# esp32_phiccamdien.net
KiCad netlist of a schematic drawn in EasyEDA Pro
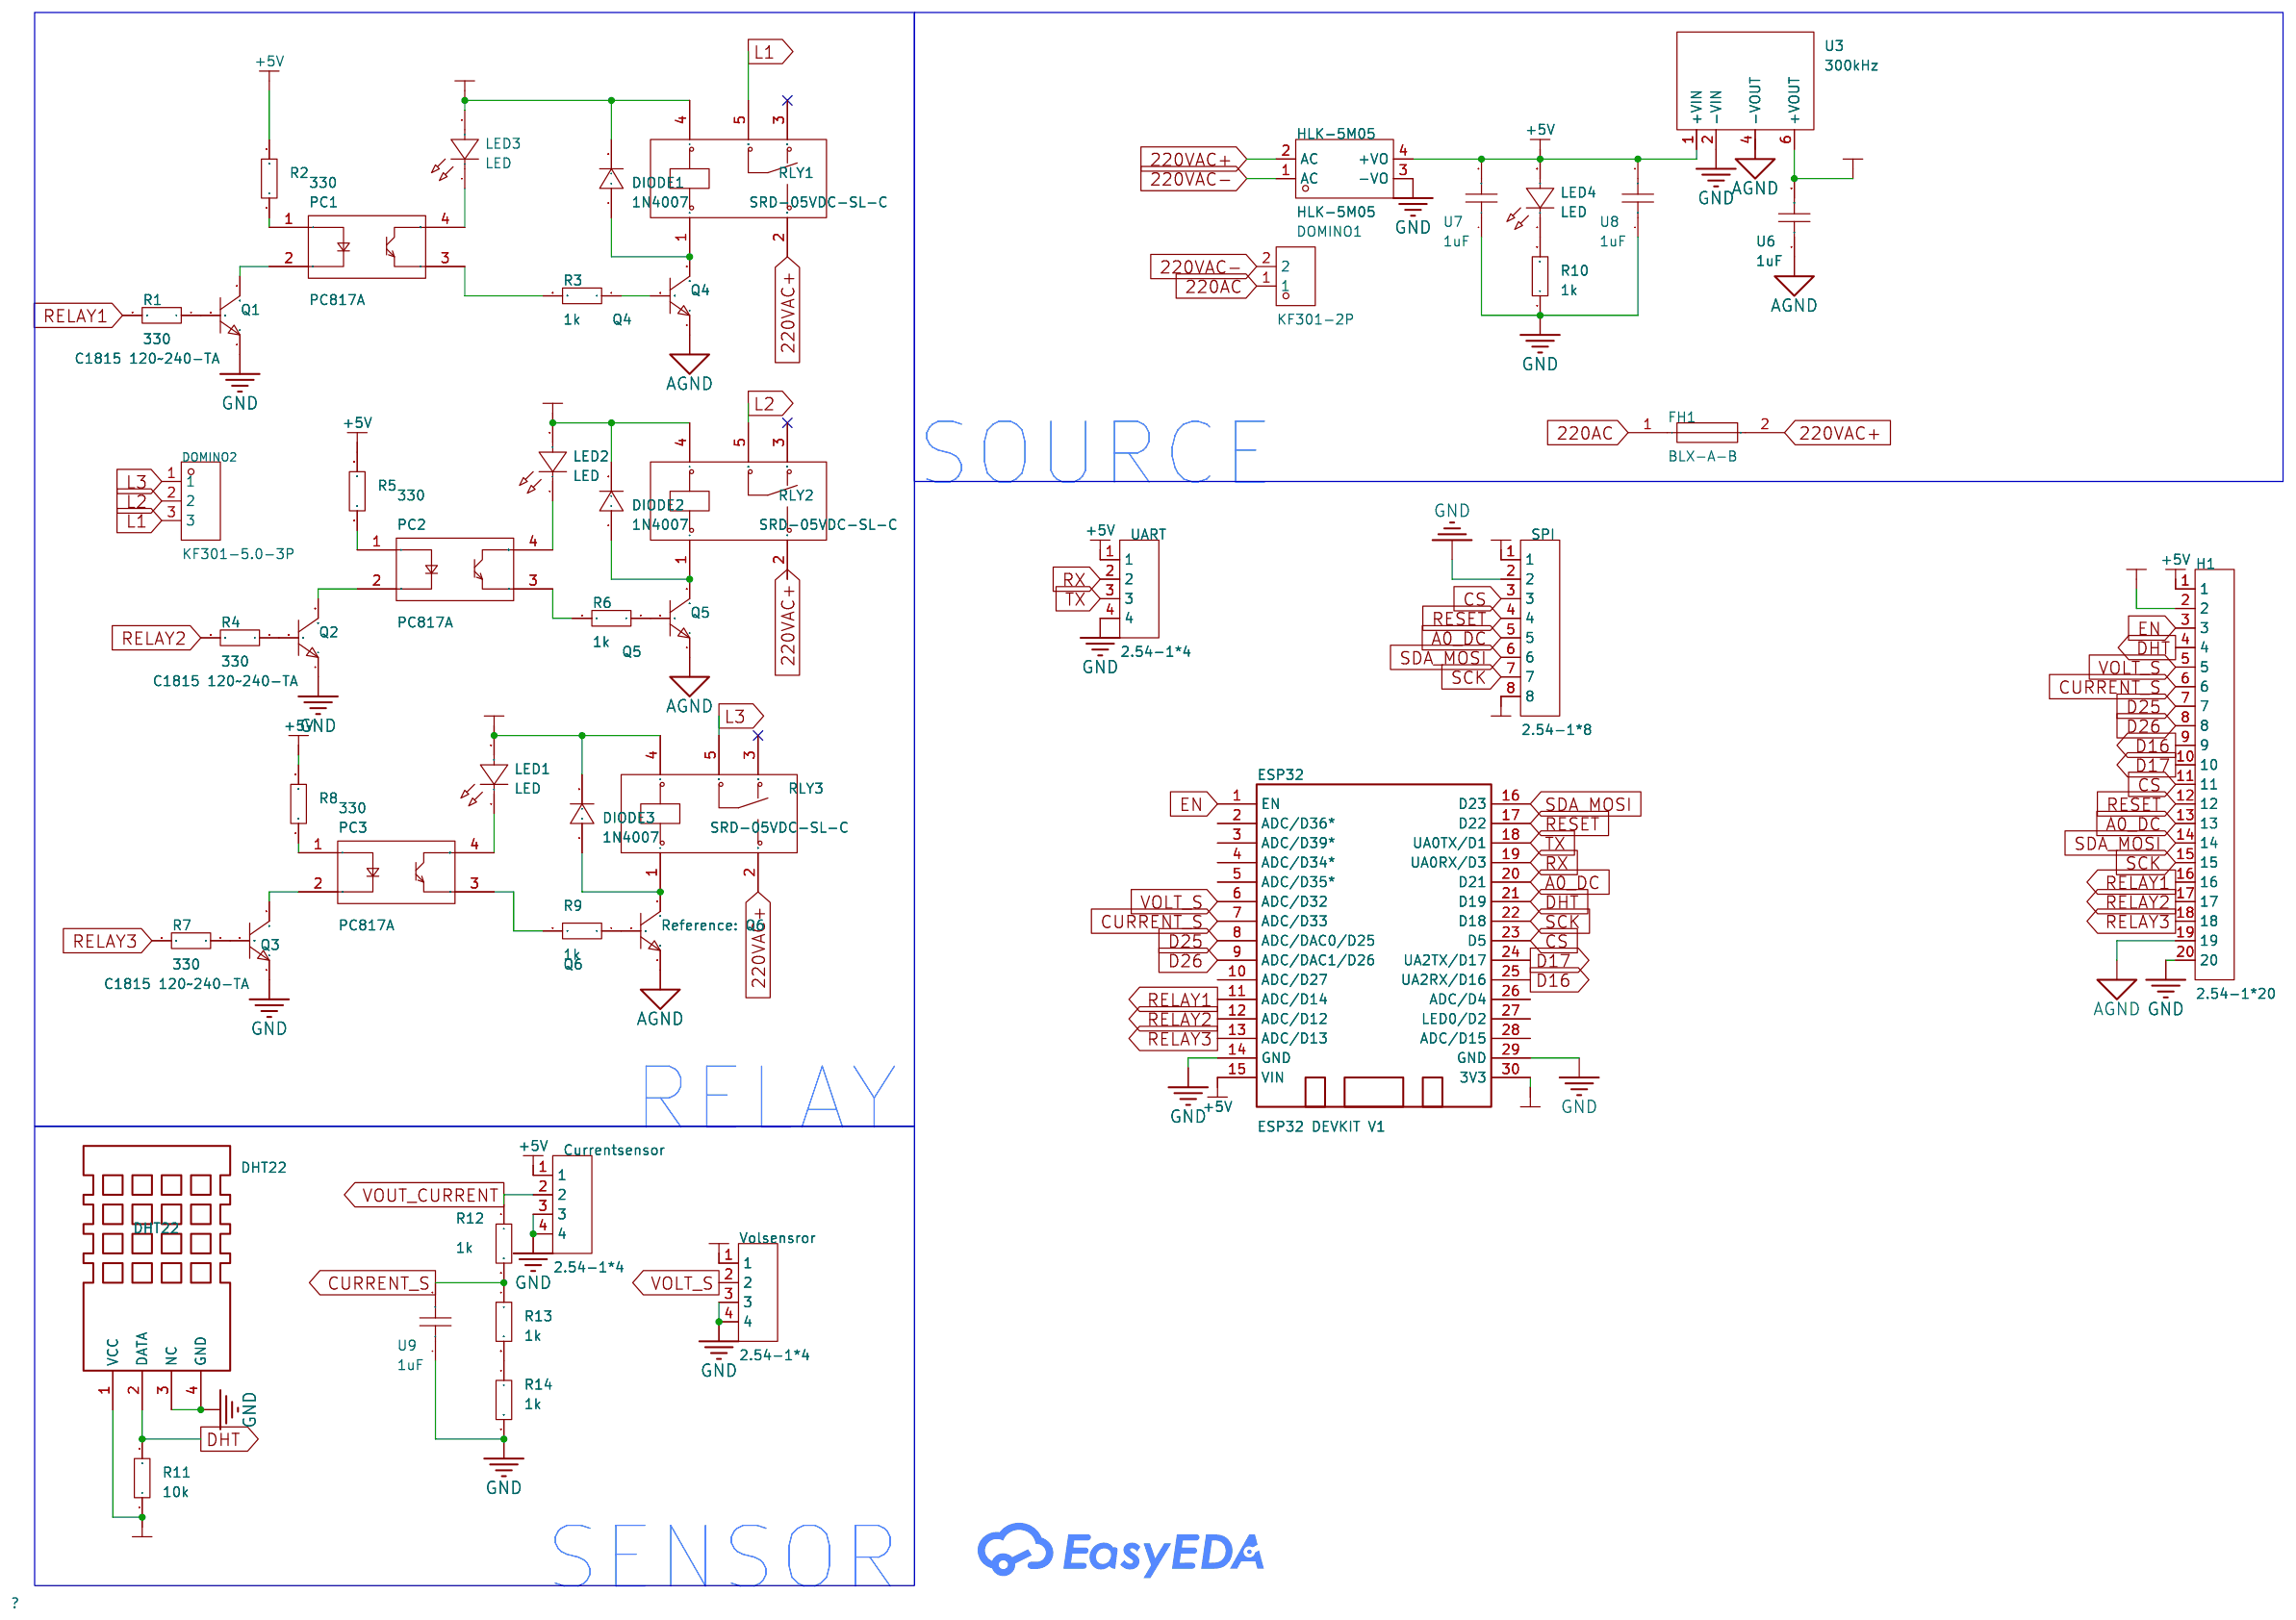
[diagram p0: schematic sheet]

(export (version "E")
  (design (tool "Eeschema 10.0.6"))
  (components
    (comp (ref "Currentsensor")
      (value "2.54-1*4")
      (footprint "easyedapro:HDR-TH_4P-P2.54-V-M-1")
      (fields (field (name "Manufacturer") "ZHOURI(洲日)"))
      (libsource (lib "easyedapro") (part "2.54-1*4"))
    )
    (comp (ref "DHT22")
      (value "DHT22")
      (footprint "easyedapro:DHT22_AM2303_VERT")
      (fields (field (name "Manufacturer") "Aosong (Guangzhou) Electronics Co., Ltd."))
      (libsource (lib "easyedapro") (part "DHT22"))
    )
    (comp (ref "DIODE1")
      (value "1N4007")
      (footprint "easyedapro:DO-41_BD2.4-L4.7-P8.70-D0.9-FD")
      (fields (field (name "Manufacturer") "EIC"))
      (libsource (lib "easyedapro") (part "1N4007_C2978779"))
    )
    (comp (ref "DIODE2")
      (value "1N4007")
      (footprint "easyedapro:DO-41_BD2.4-L4.7-P8.70-D0.9-FD")
      (fields (field (name "Manufacturer") "EIC"))
      (libsource (lib "easyedapro") (part "1N4007_C2978779"))
    )
    (comp (ref "DIODE3")
      (value "1N4007")
      (footprint "easyedapro:DO-41_BD2.4-L4.7-P8.70-D0.9-FD")
      (fields (field (name "Manufacturer") "EIC"))
      (libsource (lib "easyedapro") (part "1N4007_C2978779"))
    )
    (comp (ref "DOMINO1")
      (value "KF301-2P")
      (footprint "easyedapro:CONN-TH_XY301V-A-5.0-2P")
      (libsource (lib "easyedapro") (part "KF301-2P接线端子"))
    )
    (comp (ref "DOMINO2")
      (value "KF301-5.0-3P")
      (footprint "easyedapro:CONN-TH_3P-P5.00_KF301-5.0-3P")
      (fields (field (name "Manufacturer") "KEFA(科发)"))
      (libsource (lib "easyedapro") (part "KF301-5.0-3P"))
    )
    (comp (ref "ESP32")
      (value "ESP32 DEVKIT V1")
      (footprint "easyedapro:DOIT-ESP32-DEVKIT-V1")
      (libsource (lib "easyedapro") (part "essssp32"))
    )
    (comp (ref "FH1")
      (value "BLX-A-B")
      (footprint "easyedapro:FUSE-TH_BLX-A-B")
      (description "Voltage Rating:500V Current Rating:10A")
      (fields (field (name "Manufacturer") "XFCN(兴飞)"))
      (libsource (lib "easyedapro") (part "BLX-A-B"))
    )
    (comp (ref "H1")
      (value "2.54-1*20")
      (footprint "easyedapro:HDR-TH_20P-P2.54-V-M")
      (fields (field (name "Manufacturer") "ZHOURI(洲日)"))
      (libsource (lib "easyedapro") (part "2.54-1*20"))
    )
    (comp (ref "HLK-5M05")
      (value "HLK-5M05")
      (footprint "easyedapro:PWRM-TH_HLK-5M05")
      (fields (field (name "Manufacturer") "HI-LINK(海凌科)"))
      (libsource (lib "easyedapro") (part "HLK-5M05"))
    )
    (comp (ref "LED1")
      (value "LED")
      (footprint "easyedapro:LED0603-RD_RED")
      (libsource (lib "easyedapro") (part "贴片LED_C9900008255"))
    )
    (comp (ref "LED2")
      (value "LED")
      (footprint "easyedapro:LED0603-RD_RED")
      (libsource (lib "easyedapro") (part "贴片LED_C9900008255"))
    )
    (comp (ref "LED3")
      (value "LED")
      (footprint "easyedapro:LED0603-RD_RED")
      (libsource (lib "easyedapro") (part "贴片LED_C9900008255"))
    )
    (comp (ref "LED4")
      (value "LED")
      (footprint "easyedapro:LED0603-RD_RED")
      (libsource (lib "easyedapro") (part "贴片LED_C9900008255"))
    )
    (comp (ref "PC1")
      (value "PC817A")
      (footprint "easyedapro:DIP-4_L4.6-W6.5-P2.54-LS7.6-BL")
      (fields (field (name "Manufacturer") "GOODWORK(固得沃克)"))
      (libsource (lib "easyedapro") (part "PC817A"))
    )
    (comp (ref "PC2")
      (value "PC817A")
      (footprint "easyedapro:DIP-4_L4.6-W6.5-P2.54-LS7.6-BL")
      (fields (field (name "Manufacturer") "GOODWORK(固得沃克)"))
      (libsource (lib "easyedapro") (part "PC817A"))
    )
    (comp (ref "PC3")
      (value "PC817A")
      (footprint "easyedapro:DIP-4_L4.6-W6.5-P2.54-LS7.6-BL")
      (fields (field (name "Manufacturer") "GOODWORK(固得沃克)"))
      (libsource (lib "easyedapro") (part "PC817A"))
    )
    (comp (ref "Q1")
      (value "C1815 120~240-TA")
      (footprint "easyedapro:TO-92-3_L4.9-W3.7-P1.27-L")
      (fields (field (name "Manufacturer") "CJ(江苏长电/长晶)"))
      (libsource (lib "easyedapro") (part "C1815 120~240-TA"))
    )
    (comp (ref "Q2")
      (value "C1815 120~240-TA")
      (footprint "easyedapro:TO-92-3_L4.9-W3.7-P1.27-L")
      (fields (field (name "Manufacturer") "CJ(江苏长电/长晶)"))
      (libsource (lib "easyedapro") (part "C1815 120~240-TA"))
    )
    (comp (ref "Q3")
      (value "C1815 120~240-TA")
      (footprint "easyedapro:TO-92-3_L4.9-W3.7-P1.27-L")
      (fields (field (name "Manufacturer") "CJ(江苏长电/长晶)"))
      (libsource (lib "easyedapro") (part "C1815 120~240-TA"))
    )
    (comp (ref "Q4")
      (value "Q4")
      (footprint "easyedapro:TO-92-3_L4.9-W3.7-P1.27-L")
      (fields (field (name "Manufacturer") "CJ(江苏长电/长晶)"))
      (libsource (lib "easyedapro") (part "C1815 120~240-TA"))
    )
    (comp (ref "Q5")
      (value "Q5")
      (footprint "easyedapro:TO-92-3_L4.9-W3.7-P1.27-L")
      (fields (field (name "Manufacturer") "CJ(江苏长电/长晶)"))
      (libsource (lib "easyedapro") (part "C1815 120~240-TA"))
    )
    (comp (ref "Q6")
      (value "Q6")
      (footprint "easyedapro:TO-92-3_L4.9-W3.7-P1.27-L")
      (fields (field (name "Manufacturer") "CJ(江苏长电/长晶)"))
      (libsource (lib "easyedapro") (part "C1815 120~240-TA"))
    )
    (comp (ref "R1") (value "330") (footprint "easyedapro:R0603") (libsource (lib "easyedapro") (part "Res")))
    (comp (ref "R2") (value "330") (footprint "easyedapro:R0603") (libsource (lib "easyedapro") (part "Res")))
    (comp (ref "R3") (value "1k") (footprint "easyedapro:R0603") (libsource (lib "easyedapro") (part "Res")))
    (comp (ref "R4") (value "330") (footprint "easyedapro:R0603") (libsource (lib "easyedapro") (part "Res")))
    (comp (ref "R5") (value "330") (footprint "easyedapro:R0603") (libsource (lib "easyedapro") (part "Res")))
    (comp (ref "R6") (value "1k") (footprint "easyedapro:R0603") (libsource (lib "easyedapro") (part "Res")))
    (comp (ref "R7") (value "330") (footprint "easyedapro:R0603") (libsource (lib "easyedapro") (part "Res")))
    (comp (ref "R8") (value "330") (footprint "easyedapro:R0603") (libsource (lib "easyedapro") (part "Res")))
    (comp (ref "R9") (value "1k") (footprint "easyedapro:R0603") (libsource (lib "easyedapro") (part "Res")))
    (comp (ref "R10") (value "1k") (footprint "easyedapro:R0603") (libsource (lib "easyedapro") (part "Res")))
    (comp (ref "R11")
      (value "10k")
      (footprint "easyedapro:R0603")
      (libsource (lib "easyedapro") (part "Res"))
    )
    (comp (ref "R12") (value "1k") (footprint "easyedapro:R0603") (libsource (lib "easyedapro") (part "Res")))
    (comp (ref "R13") (value "1k") (footprint "easyedapro:R0603") (libsource (lib "easyedapro") (part "Res")))
    (comp (ref "R14") (value "1k") (footprint "easyedapro:R0603") (libsource (lib "easyedapro") (part "Res")))
    (comp (ref "RLY1")
      (value "SRD-05VDC-SL-C")
      (footprint "easyedapro:RELAY-TH_SRD-XXVDC-XL-C")
      (fields (field (name "Manufacturer") "松乐"))
      (libsource (lib "easyedapro") (part "SRD-05VDC-SL-C"))
    )
    (comp (ref "RLY2")
      (value "SRD-05VDC-SL-C")
      (footprint "easyedapro:RELAY-TH_SRD-XXVDC-XL-C")
      (fields (field (name "Manufacturer") "松乐"))
      (libsource (lib "easyedapro") (part "SRD-05VDC-SL-C"))
    )
    (comp (ref "RLY3")
      (value "SRD-05VDC-SL-C")
      (footprint "easyedapro:RELAY-TH_SRD-XXVDC-XL-C")
      (fields (field (name "Manufacturer") "松乐"))
      (libsource (lib "easyedapro") (part "SRD-05VDC-SL-C"))
    )
    (comp (ref "SPI")
      (value "2.54-1*8")
      (footprint "easyedapro:HDR-TH_8P-P2.54-V-M")
      (fields (field (name "Manufacturer") "ZHOURI(洲日)"))
      (libsource (lib "easyedapro") (part "2.54-1*8"))
    )
    (comp (ref "U3")
      (value "300kHz")
      (footprint "easyedapro:PWRM-TH_4P-L19.5-W7.0-P2.54")
      (fields (field (name "Manufacturer Part") "B0505S-2W") (field (name "Manufacturer") "YLPTEC(易川)"))
      (libsource (lib "easyedapro") (part "B0505S-2W_C22749780"))
    )
    (comp (ref "U6")
      (value "1uF")
      (footprint "easyedapro:C0402")
      (libsource (lib "easyedapro") (part "GRM155R71E103KA01D | SMD CERAMIC CAPACITOR"))
    )
    (comp (ref "U7")
      (value "1uF")
      (footprint "easyedapro:C0402")
      (libsource (lib "easyedapro") (part "GRM155R71E103KA01D | SMD CERAMIC CAPACITOR"))
    )
    (comp (ref "U8")
      (value "1uF")
      (footprint "easyedapro:C0402")
      (libsource (lib "easyedapro") (part "GRM155R71E103KA01D | SMD CERAMIC CAPACITOR"))
    )
    (comp (ref "U9")
      (value "1uF")
      (footprint "easyedapro:C0402")
      (libsource (lib "easyedapro") (part "GRM155R71E103KA01D | SMD CERAMIC CAPACITOR"))
    )
    (comp (ref "UART")
      (value "2.54-1*4")
      (footprint "easyedapro:HDR-TH_4P-P2.54-V-M-1")
      (fields (field (name "Manufacturer") "ZHOURI(洲日)"))
      (libsource (lib "easyedapro") (part "2.54-1*4"))
    )
    (comp (ref "Volsensror")
      (value "2.54-1*4")
      (footprint "easyedapro:HDR-TH_4P-P2.54-V-M-1")
      (fields (field (name "Manufacturer") "ZHOURI(洲日)"))
      (libsource (lib "easyedapro") (part "2.54-1*4"))
    )
  )
  (nets
    (net (code "1") (name "+3.3V") (class "Default")
      (node (ref "DHT22") (pin "1") (pinfunction "VCC_1") (pintype "unspecified"))
      (node (ref "ESP32") (pin "30") (pinfunction "3V3_30") (pintype "bidirectional"))
      (node (ref "H1") (pin "2") (pinfunction "2_2") (pintype "unspecified"))
      (node (ref "R11") (pin "1") (pinfunction "1_1") (pintype "input"))
      (node (ref "SPI") (pin "1") (pinfunction "1_1") (pintype "unspecified"))
      (node (ref "SPI") (pin "8") (pinfunction "8_8") (pintype "unspecified"))
      (node (ref "Volsensror") (pin "1") (pinfunction "1_1") (pintype "unspecified"))
    )
    (net (code "2") (name "+5.0V") (class "Default")
      (node (ref "DIODE1") (pin "2") (pinfunction "K_2") (pintype "unspecified"))
      (node (ref "DIODE2") (pin "2") (pinfunction "K_2") (pintype "unspecified"))
      (node (ref "DIODE3") (pin "2") (pinfunction "K_2") (pintype "unspecified"))
      (node (ref "LED1") (pin "2") (pinfunction "A_2") (pintype "unspecified"))
      (node (ref "LED2") (pin "2") (pinfunction "A_2") (pintype "unspecified"))
      (node (ref "LED3") (pin "2") (pinfunction "A_2") (pintype "unspecified"))
      (node (ref "RLY1") (pin "4") (pinfunction "4_4") (pintype "input"))
      (node (ref "RLY2") (pin "4") (pinfunction "4_4") (pintype "input"))
      (node (ref "RLY3") (pin "4") (pinfunction "4_4") (pintype "input"))
      (node (ref "U3") (pin "6") (pinfunction "+VOUT_6") (pintype "unspecified"))
      (node (ref "U6") (pin "2") (pinfunction "2_2") (pintype "unspecified"))
    )
    (net (code "3") (name "+5V") (class "Default")
      (node (ref "Currentsensor") (pin "1") (pinfunction "1_1") (pintype "unspecified"))
      (node (ref "ESP32") (pin "15") (pinfunction "VIN_15") (pintype "input"))
      (node (ref "H1") (pin "1") (pinfunction "1_1") (pintype "unspecified"))
      (node (ref "HLK-5M05") (pin "4") (pinfunction "+VO_4") (pintype "unspecified"))
      (node (ref "LED4") (pin "2") (pinfunction "A_2") (pintype "unspecified"))
      (node (ref "R2") (pin "2") (pinfunction "2_2") (pintype "input"))
      (node (ref "R5") (pin "2") (pinfunction "2_2") (pintype "input"))
      (node (ref "R8") (pin "2") (pinfunction "2_2") (pintype "input"))
      (node (ref "U3") (pin "1") (pinfunction "+VIN_1") (pintype "unspecified"))
      (node (ref "U7") (pin "2") (pinfunction "2_2") (pintype "unspecified"))
      (node (ref "U8") (pin "2") (pinfunction "2_2") (pintype "unspecified"))
      (node (ref "UART") (pin "1") (pinfunction "1_1") (pintype "unspecified"))
    )
    (net (code "4") (name "220AC") (class "Default")
      (node (ref "DOMINO1") (pin "1") (pinfunction "1_1") (pintype "unspecified"))
      (node (ref "FH1") (pin "1") (pinfunction "1_1") (pintype "unspecified"))
    )
    (net (code "5") (name "220VAC+") (class "Default")
      (node (ref "FH1") (pin "2") (pinfunction "2_2") (pintype "unspecified"))
      (node (ref "HLK-5M05") (pin "2") (pinfunction "AC_2") (pintype "unspecified"))
      (node (ref "RLY1") (pin "2") (pinfunction "2_2") (pintype "input"))
      (node (ref "RLY2") (pin "2") (pinfunction "2_2") (pintype "input"))
      (node (ref "RLY3") (pin "2") (pinfunction "2_2") (pintype "input"))
    )
    (net (code "6") (name "220VAC-") (class "Default")
      (node (ref "DOMINO1") (pin "2") (pinfunction "2_2") (pintype "unspecified"))
      (node (ref "HLK-5M05") (pin "1") (pinfunction "AC_1") (pintype "unspecified"))
    )
    (net (code "7") (name "A0_DC") (class "Default")
      (node (ref "ESP32") (pin "20") (pinfunction "D21_20") (pintype "bidirectional"))
      (node (ref "H1") (pin "13") (pinfunction "13_13") (pintype "unspecified"))
      (node (ref "SPI") (pin "5") (pinfunction "5_5") (pintype "unspecified"))
    )
    (net (code "8") (name "AGND") (class "Default")
      (node (ref "H1") (pin "19") (pinfunction "19_19") (pintype "unspecified"))
      (node (ref "Q4") (pin "1") (pinfunction "E_1") (pintype "unspecified"))
      (node (ref "Q5") (pin "1") (pinfunction "E_1") (pintype "unspecified"))
      (node (ref "Q6") (pin "1") (pinfunction "E_1") (pintype "unspecified"))
      (node (ref "U3") (pin "4") (pinfunction "-VOUT_4") (pintype "unspecified"))
      (node (ref "U6") (pin "1") (pinfunction "1_1") (pintype "unspecified"))
    )
    (net (code "9") (name "CS") (class "Default")
      (node (ref "ESP32") (pin "23") (pinfunction "D5_23") (pintype "bidirectional"))
      (node (ref "H1") (pin "11") (pinfunction "11_11") (pintype "unspecified"))
      (node (ref "SPI") (pin "3") (pinfunction "3_3") (pintype "unspecified"))
    )
    (net (code "10") (name "CURRENT_S") (class "Default")
      (node (ref "ESP32") (pin "7") (pinfunction "ADC/D33_7") (pintype "bidirectional"))
      (node (ref "H1") (pin "6") (pinfunction "6_6") (pintype "unspecified"))
      (node (ref "R12") (pin "2") (pinfunction "2_2") (pintype "input"))
      (node (ref "R13") (pin "1") (pinfunction "1_1") (pintype "input"))
      (node (ref "U9") (pin "2") (pinfunction "2_2") (pintype "unspecified"))
    )
    (net (code "11") (name "D16") (class "Default")
      (node (ref "ESP32") (pin "25") (pinfunction "UA2RX/D16_25") (pintype "bidirectional"))
      (node (ref "H1") (pin "9") (pinfunction "9_9") (pintype "unspecified"))
    )
    (net (code "12") (name "D17") (class "Default")
      (node (ref "ESP32") (pin "24") (pinfunction "UA2TX/D17_24") (pintype "bidirectional"))
      (node (ref "H1") (pin "10") (pinfunction "10_10") (pintype "unspecified"))
    )
    (net (code "13") (name "D25") (class "Default")
      (node (ref "ESP32") (pin "8") (pinfunction "ADC/DAC0/D25_8") (pintype "bidirectional"))
      (node (ref "H1") (pin "7") (pinfunction "7_7") (pintype "unspecified"))
    )
    (net (code "14") (name "D26") (class "Default")
      (node (ref "ESP32") (pin "9") (pinfunction "ADC/DAC1/D26_9") (pintype "bidirectional"))
      (node (ref "H1") (pin "8") (pinfunction "8_8") (pintype "unspecified"))
    )
    (net (code "15") (name "DHT") (class "Default")
      (node (ref "DHT22") (pin "2") (pinfunction "DATA_2") (pintype "unspecified"))
      (node (ref "ESP32") (pin "21") (pinfunction "D19_21") (pintype "bidirectional"))
      (node (ref "H1") (pin "4") (pinfunction "4_4") (pintype "unspecified"))
      (node (ref "R11") (pin "2") (pinfunction "2_2") (pintype "input"))
    )
    (net (code "16") (name "EN") (class "Default")
      (node (ref "ESP32") (pin "1") (pinfunction "EN_1") (pintype "bidirectional"))
      (node (ref "H1") (pin "3") (pinfunction "3_3") (pintype "unspecified"))
    )
    (net (code "17") (name "GND") (class "Default")
      (node (ref "Currentsensor") (pin "3") (pinfunction "3_3") (pintype "unspecified"))
      (node (ref "Currentsensor") (pin "4") (pinfunction "4_4") (pintype "unspecified"))
      (node (ref "DHT22") (pin "3") (pinfunction "NC_3") (pintype "unspecified"))
      (node (ref "DHT22") (pin "4") (pinfunction "GND_4") (pintype "unspecified"))
      (node (ref "ESP32") (pin "14") (pinfunction "GND_14") (pintype "bidirectional"))
      (node (ref "ESP32") (pin "29") (pinfunction "GND_29") (pintype "bidirectional"))
      (node (ref "H1") (pin "20") (pinfunction "20_20") (pintype "unspecified"))
      (node (ref "HLK-5M05") (pin "3") (pinfunction "-VO_3") (pintype "unspecified"))
      (node (ref "Q1") (pin "1") (pinfunction "E_1") (pintype "unspecified"))
      (node (ref "Q2") (pin "1") (pinfunction "E_1") (pintype "unspecified"))
      (node (ref "Q3") (pin "1") (pinfunction "E_1") (pintype "unspecified"))
      (node (ref "R10") (pin "1") (pinfunction "1_1") (pintype "input"))
      (node (ref "R14") (pin "2") (pinfunction "2_2") (pintype "input"))
      (node (ref "SPI") (pin "2") (pinfunction "2_2") (pintype "unspecified"))
      (node (ref "U3") (pin "2") (pinfunction "-VIN_2") (pintype "unspecified"))
      (node (ref "U7") (pin "1") (pinfunction "1_1") (pintype "unspecified"))
      (node (ref "U8") (pin "1") (pinfunction "1_1") (pintype "unspecified"))
      (node (ref "U9") (pin "1") (pinfunction "1_1") (pintype "unspecified"))
      (node (ref "UART") (pin "4") (pinfunction "4_4") (pintype "unspecified"))
      (node (ref "Volsensror") (pin "3") (pinfunction "3_3") (pintype "unspecified"))
      (node (ref "Volsensror") (pin "4") (pinfunction "4_4") (pintype "unspecified"))
    )
    (net (code "18") (name "L1") (class "Default")
      (node (ref "DOMINO2") (pin "3") (pinfunction "3_3") (pintype "input"))
      (node (ref "RLY1") (pin "5") (pinfunction "5_5") (pintype "input"))
    )
    (net (code "19") (name "L2") (class "Default")
      (node (ref "DOMINO2") (pin "2") (pinfunction "2_2") (pintype "input"))
      (node (ref "RLY2") (pin "5") (pinfunction "5_5") (pintype "input"))
    )
    (net (code "20") (name "L3") (class "Default")
      (node (ref "DOMINO2") (pin "1") (pinfunction "1_1") (pintype "input"))
      (node (ref "RLY3") (pin "5") (pinfunction "5_5") (pintype "input"))
    )
    (net (code "21") (name "Net-(DIODE1-A)") (class "Default")
      (node (ref "DIODE1") (pin "1") (pinfunction "A_1") (pintype "unspecified"))
      (node (ref "Q4") (pin "2") (pinfunction "C_2") (pintype "unspecified"))
      (node (ref "RLY1") (pin "1") (pinfunction "1_1") (pintype "input"))
    )
    (net (code "22") (name "Net-(DIODE2-A)") (class "Default")
      (node (ref "DIODE2") (pin "1") (pinfunction "A_1") (pintype "unspecified"))
      (node (ref "Q5") (pin "2") (pinfunction "C_2") (pintype "unspecified"))
      (node (ref "RLY2") (pin "1") (pinfunction "1_1") (pintype "input"))
    )
    (net (code "23") (name "Net-(DIODE3-A)") (class "Default")
      (node (ref "DIODE3") (pin "1") (pinfunction "A_1") (pintype "unspecified"))
      (node (ref "Q6") (pin "2") (pinfunction "C_2") (pintype "unspecified"))
      (node (ref "RLY3") (pin "1") (pinfunction "1_1") (pintype "input"))
    )
    (net (code "24") (name "Net-(LED1-K)") (class "Default")
      (node (ref "LED1") (pin "1") (pinfunction "K_1") (pintype "unspecified"))
      (node (ref "PC3") (pin "4") (pinfunction "COL_4") (pintype "unspecified"))
    )
    (net (code "25") (name "Net-(LED2-K)") (class "Default")
      (node (ref "LED2") (pin "1") (pinfunction "K_1") (pintype "unspecified"))
      (node (ref "PC2") (pin "4") (pinfunction "COL_4") (pintype "unspecified"))
    )
    (net (code "26") (name "Net-(LED3-K)") (class "Default")
      (node (ref "LED3") (pin "1") (pinfunction "K_1") (pintype "unspecified"))
      (node (ref "PC1") (pin "4") (pinfunction "COL_4") (pintype "unspecified"))
    )
    (net (code "27") (name "Net-(LED4-K)") (class "Default")
      (node (ref "LED4") (pin "1") (pinfunction "K_1") (pintype "unspecified"))
      (node (ref "R10") (pin "2") (pinfunction "2_2") (pintype "input"))
    )
    (net (code "28") (name "Net-(PC1-A)") (class "Default")
      (node (ref "PC1") (pin "1") (pinfunction "A_1") (pintype "unspecified"))
      (node (ref "R2") (pin "1") (pinfunction "1_1") (pintype "input"))
    )
    (net (code "29") (name "Net-(PC1-C)") (class "Default")
      (node (ref "PC1") (pin "2") (pinfunction "C_2") (pintype "unspecified"))
      (node (ref "Q1") (pin "2") (pinfunction "C_2") (pintype "unspecified"))
    )
    (net (code "30") (name "Net-(PC1-EM)") (class "Default")
      (node (ref "PC1") (pin "3") (pinfunction "EM_3") (pintype "unspecified"))
      (node (ref "R3") (pin "2") (pinfunction "2_2") (pintype "input"))
    )
    (net (code "31") (name "Net-(PC2-A)") (class "Default")
      (node (ref "PC2") (pin "1") (pinfunction "A_1") (pintype "unspecified"))
      (node (ref "R5") (pin "1") (pinfunction "1_1") (pintype "input"))
    )
    (net (code "32") (name "Net-(PC2-C)") (class "Default")
      (node (ref "PC2") (pin "2") (pinfunction "C_2") (pintype "unspecified"))
      (node (ref "Q2") (pin "2") (pinfunction "C_2") (pintype "unspecified"))
    )
    (net (code "33") (name "Net-(PC2-EM)") (class "Default")
      (node (ref "PC2") (pin "3") (pinfunction "EM_3") (pintype "unspecified"))
      (node (ref "R6") (pin "2") (pinfunction "2_2") (pintype "input"))
    )
    (net (code "34") (name "Net-(PC3-A)") (class "Default")
      (node (ref "PC3") (pin "1") (pinfunction "A_1") (pintype "unspecified"))
      (node (ref "R8") (pin "1") (pinfunction "1_1") (pintype "input"))
    )
    (net (code "35") (name "Net-(PC3-C)") (class "Default")
      (node (ref "PC3") (pin "2") (pinfunction "C_2") (pintype "unspecified"))
      (node (ref "Q3") (pin "2") (pinfunction "C_2") (pintype "unspecified"))
    )
    (net (code "36") (name "Net-(PC3-EM)") (class "Default")
      (node (ref "PC3") (pin "3") (pinfunction "EM_3") (pintype "unspecified"))
      (node (ref "R9") (pin "2") (pinfunction "2_2") (pintype "input"))
    )
    (net (code "37") (name "Net-(Q1-B)") (class "Default")
      (node (ref "Q1") (pin "3") (pinfunction "B_3") (pintype "unspecified"))
      (node (ref "R1") (pin "1") (pinfunction "1_1") (pintype "input"))
    )
    (net (code "38") (name "Net-(Q2-B)") (class "Default")
      (node (ref "Q2") (pin "3") (pinfunction "B_3") (pintype "unspecified"))
      (node (ref "R4") (pin "1") (pinfunction "1_1") (pintype "input"))
    )
    (net (code "39") (name "Net-(Q3-B)") (class "Default")
      (node (ref "Q3") (pin "3") (pinfunction "B_3") (pintype "unspecified"))
      (node (ref "R7") (pin "1") (pinfunction "1_1") (pintype "input"))
    )
    (net (code "40") (name "Net-(Q4-B)") (class "Default")
      (node (ref "Q4") (pin "3") (pinfunction "B_3") (pintype "unspecified"))
      (node (ref "R3") (pin "1") (pinfunction "1_1") (pintype "input"))
    )
    (net (code "41") (name "Net-(Q5-B)") (class "Default")
      (node (ref "Q5") (pin "3") (pinfunction "B_3") (pintype "unspecified"))
      (node (ref "R6") (pin "1") (pinfunction "1_1") (pintype "input"))
    )
    (net (code "42") (name "Net-(Q6-B)") (class "Default")
      (node (ref "Q6") (pin "3") (pinfunction "B_3") (pintype "unspecified"))
      (node (ref "R9") (pin "1") (pinfunction "1_1") (pintype "input"))
    )
    (net (code "43") (name "Net-(R13-Pad2)") (class "Default")
      (node (ref "R13") (pin "2") (pinfunction "2_2") (pintype "input"))
      (node (ref "R14") (pin "1") (pinfunction "1_1") (pintype "input"))
    )
    (net (code "44") (name "RELAY1") (class "Default")
      (node (ref "ESP32") (pin "11") (pinfunction "ADC/D14_11") (pintype "bidirectional"))
      (node (ref "H1") (pin "16") (pinfunction "16_16") (pintype "unspecified"))
      (node (ref "R1") (pin "2") (pinfunction "2_2") (pintype "input"))
    )
    (net (code "45") (name "RELAY2") (class "Default")
      (node (ref "ESP32") (pin "12") (pinfunction "ADC/D12_12") (pintype "bidirectional"))
      (node (ref "H1") (pin "17") (pinfunction "17_17") (pintype "unspecified"))
      (node (ref "R4") (pin "2") (pinfunction "2_2") (pintype "input"))
    )
    (net (code "46") (name "RELAY3") (class "Default")
      (node (ref "ESP32") (pin "13") (pinfunction "ADC/D13_13") (pintype "bidirectional"))
      (node (ref "H1") (pin "18") (pinfunction "18_18") (pintype "unspecified"))
      (node (ref "R7") (pin "2") (pinfunction "2_2") (pintype "input"))
    )
    (net (code "47") (name "RESET") (class "Default")
      (node (ref "ESP32") (pin "17") (pinfunction "D22_17") (pintype "bidirectional"))
      (node (ref "H1") (pin "12") (pinfunction "12_12") (pintype "unspecified"))
      (node (ref "SPI") (pin "4") (pinfunction "4_4") (pintype "unspecified"))
    )
    (net (code "48") (name "RX") (class "Default")
      (node (ref "ESP32") (pin "19") (pinfunction "UA0RX/D3_19") (pintype "bidirectional"))
      (node (ref "UART") (pin "2") (pinfunction "2_2") (pintype "unspecified"))
    )
    (net (code "49") (name "SCK") (class "Default")
      (node (ref "ESP32") (pin "22") (pinfunction "D18_22") (pintype "bidirectional"))
      (node (ref "H1") (pin "15") (pinfunction "15_15") (pintype "unspecified"))
      (node (ref "SPI") (pin "7") (pinfunction "7_7") (pintype "unspecified"))
    )
    (net (code "50") (name "SDA_MOSI") (class "Default")
      (node (ref "ESP32") (pin "16") (pinfunction "D23_16") (pintype "bidirectional"))
      (node (ref "H1") (pin "14") (pinfunction "14_14") (pintype "unspecified"))
      (node (ref "SPI") (pin "6") (pinfunction "6_6") (pintype "unspecified"))
    )
    (net (code "51") (name "TX") (class "Default")
      (node (ref "ESP32") (pin "18") (pinfunction "UA0TX/D1_18") (pintype "bidirectional"))
      (node (ref "UART") (pin "3") (pinfunction "3_3") (pintype "unspecified"))
    )
    (net (code "52") (name "VOLT_S") (class "Default")
      (node (ref "ESP32") (pin "6") (pinfunction "ADC/D32_6") (pintype "bidirectional"))
      (node (ref "H1") (pin "5") (pinfunction "5_5") (pintype "unspecified"))
      (node (ref "Volsensror") (pin "2") (pinfunction "2_2") (pintype "unspecified"))
    )
    (net (code "53") (name "VOUT_CURRENT") (class "Default")
      (node (ref "Currentsensor") (pin "2") (pinfunction "2_2") (pintype "unspecified"))
      (node (ref "R12") (pin "1") (pinfunction "1_1") (pintype "input"))
    )
    (net (code "54") (name "unconnected-(ESP32-ADC{slash}D4-Pad26)") (class "Default")
      (node (ref "ESP32") (pin "26") (pinfunction "ADC/D4_26") (pintype "bidirectional"))
    )
    (net (code "55") (name "unconnected-(ESP32-ADC{slash}D15-Pad28)") (class "Default")
      (node (ref "ESP32") (pin "28") (pinfunction "ADC/D15_28") (pintype "bidirectional"))
    )
    (net (code "56") (name "unconnected-(ESP32-ADC{slash}D27-Pad10)") (class "Default")
      (node (ref "ESP32") (pin "10") (pinfunction "ADC/D27_10") (pintype "bidirectional"))
    )
    (net (code "57") (name "unconnected-(ESP32-ADC{slash}D34*-Pad4)") (class "Default")
      (node (ref "ESP32") (pin "4") (pinfunction "ADC/D34*_4") (pintype "input"))
    )
    (net (code "58") (name "unconnected-(ESP32-ADC{slash}D35*-Pad5)") (class "Default")
      (node (ref "ESP32") (pin "5") (pinfunction "ADC/D35*_5") (pintype "input"))
    )
    (net (code "59") (name "unconnected-(ESP32-ADC{slash}D36*-Pad2)") (class "Default")
      (node (ref "ESP32") (pin "2") (pinfunction "ADC/D36*_2") (pintype "input"))
    )
    (net (code "60") (name "unconnected-(ESP32-ADC{slash}D39*-Pad3)") (class "Default")
      (node (ref "ESP32") (pin "3") (pinfunction "ADC/D39*_3") (pintype "input"))
    )
    (net (code "61") (name "unconnected-(ESP32-LED0{slash}D2-Pad27)") (class "Default")
      (node (ref "ESP32") (pin "27") (pinfunction "LED0/D2_27") (pintype "bidirectional"))
    )
    (net (code "62") (name "unconnected-(RLY1-Pad3)") (class "Default")
      (node (ref "RLY1") (pin "3") (pinfunction "3_3") (pintype "input+no_connect"))
    )
    (net (code "63") (name "unconnected-(RLY2-Pad3)") (class "Default")
      (node (ref "RLY2") (pin "3") (pinfunction "3_3") (pintype "input+no_connect"))
    )
    (net (code "64") (name "unconnected-(RLY3-Pad3)") (class "Default")
      (node (ref "RLY3") (pin "3") (pinfunction "3_3") (pintype "input+no_connect"))
    )
  )
)
